# esp32-dev-board-v1_0.net
KiCad netlist of a schematic drawn in EasyEDA Pro
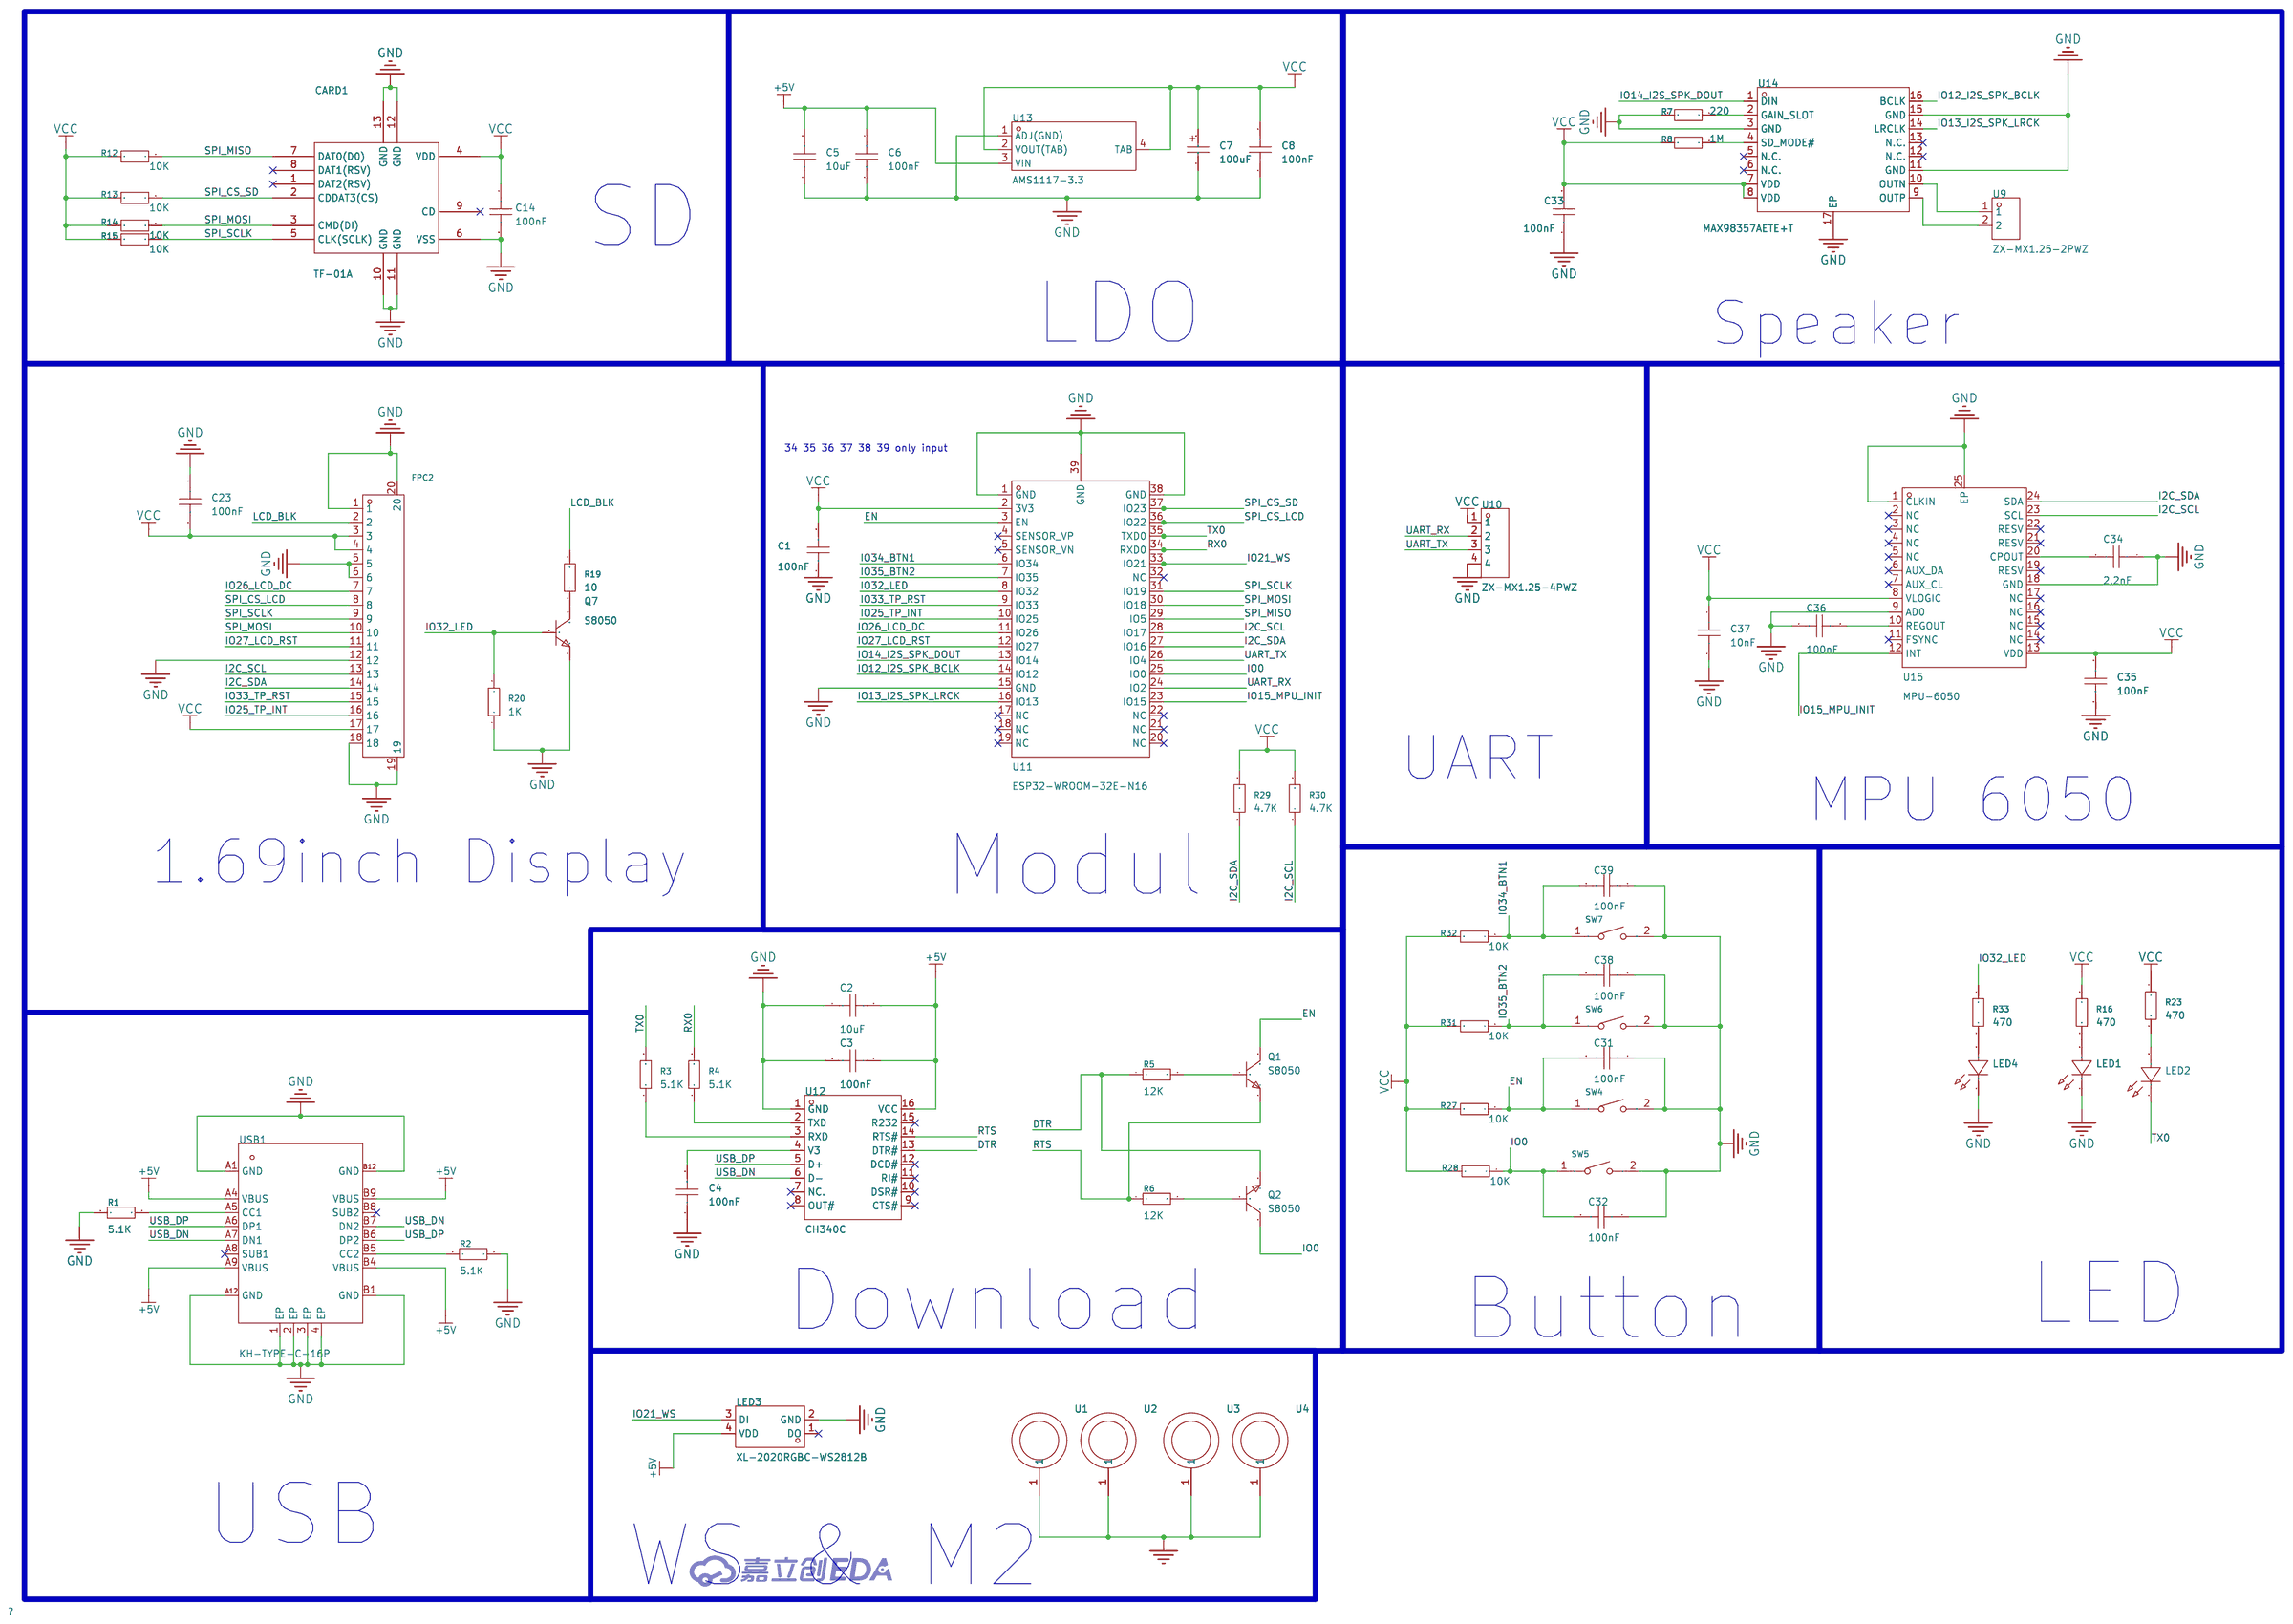
[diagram p0: schematic sheet]

(export (version "E")
  (design (tool "Eeschema 10.0.6"))
  (components
    (comp (ref "C1")
      (value "100nF")
      (footprint "easyedapro:C0402")
      (fields
        (field (name "Manufacturer Part") "CL05B104KO5NNNC")
        (field (name "Manufacturer") "SAMSUNG(三星)")
      )
      (libsource (lib "easyedapro") (part "CL05B104KO5NNNC"))
    )
    (comp (ref "C2")
      (value "10uF")
      (footprint "easyedapro:C0603")
      (fields
        (field (name "Manufacturer Part") "CGA0603X5R106K100JT")
        (field (name "Manufacturer") "HRE(芯声)")
      )
      (libsource (lib "easyedapro") (part "CGA0603X5R106K100JT"))
    )
    (comp (ref "C3")
      (value "100nF")
      (footprint "easyedapro:C0402")
      (fields
        (field (name "Manufacturer Part") "CL05B104KO5NNNC")
        (field (name "Manufacturer") "SAMSUNG(三星)")
      )
      (libsource (lib "easyedapro") (part "CL05B104KO5NNNC"))
    )
    (comp (ref "C4")
      (value "100nF")
      (footprint "easyedapro:C0402")
      (fields
        (field (name "Manufacturer Part") "CL05B104KO5NNNC")
        (field (name "Manufacturer") "SAMSUNG(三星)")
      )
      (libsource (lib "easyedapro") (part "CL05B104KO5NNNC"))
    )
    (comp (ref "C5")
      (value "10uF")
      (footprint "easyedapro:C0603")
      (fields
        (field (name "Manufacturer Part") "CGA0603X5R106K100JT")
        (field (name "Manufacturer") "HRE(芯声)")
      )
      (libsource (lib "easyedapro") (part "CGA0603X5R106K100JT"))
    )
    (comp (ref "C6")
      (value "100nF")
      (footprint "easyedapro:C0402")
      (fields
        (field (name "Manufacturer Part") "CL05B104KO5NNNC")
        (field (name "Manufacturer") "SAMSUNG(三星)")
      )
      (libsource (lib "easyedapro") (part "CL05B104KO5NNNC"))
    )
    (comp (ref "C7")
      (value "100uF")
      (footprint "easyedapro:CASE-B_3528")
      (fields (field (name "Manufacturer Part") "TAJB107K006RNJ") (field (name "Manufacturer") "Kyocera AVX"))
      (libsource (lib "easyedapro") (part "TAJB107K006RNJ"))
    )
    (comp (ref "C8")
      (value "100nF")
      (footprint "easyedapro:C0402")
      (fields
        (field (name "Manufacturer Part") "CL05B104KO5NNNC")
        (field (name "Manufacturer") "SAMSUNG(三星)")
      )
      (libsource (lib "easyedapro") (part "CL05B104KO5NNNC"))
    )
    (comp (ref "C14")
      (value "100nF")
      (footprint "easyedapro:C0402")
      (fields
        (field (name "Manufacturer Part") "CL05B104KO5NNNC")
        (field (name "Manufacturer") "SAMSUNG(三星)")
      )
      (libsource (lib "easyedapro") (part "CL05B104KO5NNNC"))
    )
    (comp (ref "C23")
      (value "100nF")
      (footprint "easyedapro:C0402")
      (fields
        (field (name "Manufacturer Part") "CL05B104KO5NNNC")
        (field (name "Manufacturer") "SAMSUNG(三星)")
      )
      (libsource (lib "easyedapro") (part "CL05B104KO5NNNC"))
    )
    (comp (ref "C31")
      (value "100nF")
      (footprint "easyedapro:C0402")
      (fields
        (field (name "Manufacturer Part") "CL05B104KO5NNNC")
        (field (name "Manufacturer") "SAMSUNG(三星)")
      )
      (libsource (lib "easyedapro") (part "CL05B104KO5NNNC"))
    )
    (comp (ref "C32")
      (value "100nF")
      (footprint "easyedapro:C0402")
      (fields
        (field (name "Manufacturer Part") "CL05B104KO5NNNC")
        (field (name "Manufacturer") "SAMSUNG(三星)")
      )
      (libsource (lib "easyedapro") (part "CL05B104KO5NNNC"))
    )
    (comp (ref "C33")
      (value "100nF")
      (footprint "easyedapro:C0402")
      (fields
        (field (name "Manufacturer Part") "CL05B104KO5NNNC")
        (field (name "Manufacturer") "SAMSUNG(三星)")
      )
      (libsource (lib "easyedapro") (part "CL05B104KO5NNNC"))
    )
    (comp (ref "C34")
      (value "2.2nF")
      (footprint "easyedapro:C0402")
      (fields
        (field (name "Manufacturer Part") "CL05B104KO5NNNC")
        (field (name "Manufacturer") "SAMSUNG(三星)")
      )
      (libsource (lib "easyedapro") (part "CL05B104KO5NNNC"))
    )
    (comp (ref "C35")
      (value "100nF")
      (footprint "easyedapro:C0402")
      (fields
        (field (name "Manufacturer Part") "CL05B104KO5NNNC")
        (field (name "Manufacturer") "SAMSUNG(三星)")
      )
      (libsource (lib "easyedapro") (part "CL05B104KO5NNNC"))
    )
    (comp (ref "C36")
      (value "100nF")
      (footprint "easyedapro:C0402")
      (fields
        (field (name "Manufacturer Part") "CL05B104KO5NNNC")
        (field (name "Manufacturer") "SAMSUNG(三星)")
      )
      (libsource (lib "easyedapro") (part "CL05B104KO5NNNC"))
    )
    (comp (ref "C37")
      (value "10nF")
      (footprint "easyedapro:C0402")
      (fields
        (field (name "Manufacturer Part") "CL05B104KO5NNNC")
        (field (name "Manufacturer") "SAMSUNG(三星)")
      )
      (libsource (lib "easyedapro") (part "CL05B104KO5NNNC"))
    )
    (comp (ref "C38")
      (value "100nF")
      (footprint "easyedapro:C0402")
      (fields
        (field (name "Manufacturer Part") "CL05B104KO5NNNC")
        (field (name "Manufacturer") "SAMSUNG(三星)")
      )
      (libsource (lib "easyedapro") (part "CL05B104KO5NNNC"))
    )
    (comp (ref "C39")
      (value "100nF")
      (footprint "easyedapro:C0402")
      (fields
        (field (name "Manufacturer Part") "CL05B104KO5NNNC")
        (field (name "Manufacturer") "SAMSUNG(三星)")
      )
      (libsource (lib "easyedapro") (part "CL05B104KO5NNNC"))
    )
    (comp (ref "CARD1")
      (value "TF-01A")
      (footprint "easyedapro:TF-SMD_TF-01A")
      (fields (field (name "Manufacturer") "韩国韩荣"))
      (libsource (lib "easyedapro") (part "TF-01A"))
    )
    (comp (ref "FPC2")
      (value "FPC-05F-18PH20")
      (footprint "easyedapro:FPC-SMD_18P-P0.50_FPC-05F-18PH20")
      (fields (field (name "Manufacturer") "XUNPU(讯普)"))
      (libsource (lib "easyedapro") (part "FPC-05F-18PH20"))
    )
    (comp (ref "LED1")
      (value "XL-1608SURC-06")
      (footprint "easyedapro:LED0603-RD_RED")
      (fields (field (name "Manufacturer") "XINGLIGHT(成兴光)"))
      (libsource (lib "easyedapro") (part "XL-1608SURC-06"))
    )
    (comp (ref "LED2")
      (value "XL-1608SURC-06")
      (footprint "easyedapro:LED0603-RD_RED")
      (fields (field (name "Manufacturer") "XINGLIGHT(成兴光)"))
      (libsource (lib "easyedapro") (part "XL-1608SURC-06"))
    )
    (comp (ref "LED3")
      (value "XL-2020RGBC-WS2812B")
      (footprint "easyedapro:LED-SMD_4P-L2.0-W2.0-BR-1")
      (fields (field (name "Manufacturer") "XINGLIGHT(成兴光)"))
      (libsource (lib "easyedapro") (part "XL-2020RGBC-WS2812B"))
    )
    (comp (ref "LED4")
      (value "XL-1608SURC-06")
      (footprint "easyedapro:LED0603-RD_RED")
      (fields (field (name "Manufacturer") "XINGLIGHT(成兴光)"))
      (libsource (lib "easyedapro") (part "XL-1608SURC-06"))
    )
    (comp (ref "Q1")
      (value "S8050")
      (footprint "easyedapro:SOT-23-3_L2.9-W1.3-P1.90-LS2.3-BR")
      (fields (field (name "Manufacturer") "宏迦橙"))
      (libsource (lib "easyedapro") (part "S8050_C20069125"))
    )
    (comp (ref "Q2")
      (value "S8050")
      (footprint "easyedapro:SOT-23-3_L2.9-W1.3-P1.90-LS2.3-BR")
      (fields (field (name "Manufacturer") "宏迦橙"))
      (libsource (lib "easyedapro") (part "S8050_C20069125"))
    )
    (comp (ref "Q7")
      (value "S8050")
      (fields (field (name "Manufacturer") "宏迦橙"))
      (libsource (lib "easyedapro") (part "S8050_C20069125"))
    )
    (comp (ref "R1")
      (value "5.1K")
      (footprint "easyedapro:R0402")
      (fields
        (field (name "Manufacturer Part") "0402WGF4700TCE")
        (field (name "Manufacturer") "UNI-ROYAL(厚声)")
      )
      (libsource (lib "easyedapro") (part "0402WGF4700TCE"))
    )
    (comp (ref "R2")
      (value "5.1K")
      (footprint "easyedapro:R0402")
      (fields
        (field (name "Manufacturer Part") "0402WGF4700TCE")
        (field (name "Manufacturer") "UNI-ROYAL(厚声)")
      )
      (libsource (lib "easyedapro") (part "0402WGF4700TCE"))
    )
    (comp (ref "R3")
      (value "5.1K")
      (footprint "easyedapro:R0402")
      (fields
        (field (name "Manufacturer Part") "0402WGF4700TCE")
        (field (name "Manufacturer") "UNI-ROYAL(厚声)")
      )
      (libsource (lib "easyedapro") (part "0402WGF4700TCE"))
    )
    (comp (ref "R4")
      (value "5.1K")
      (footprint "easyedapro:R0402")
      (fields
        (field (name "Manufacturer Part") "0402WGF4700TCE")
        (field (name "Manufacturer") "UNI-ROYAL(厚声)")
      )
      (libsource (lib "easyedapro") (part "0402WGF4700TCE"))
    )
    (comp (ref "R5")
      (value "12K")
      (footprint "easyedapro:R0402")
      (fields
        (field (name "Manufacturer Part") "0402WGF4700TCE")
        (field (name "Manufacturer") "UNI-ROYAL(厚声)")
      )
      (libsource (lib "easyedapro") (part "0402WGF4700TCE"))
    )
    (comp (ref "R6")
      (value "12K")
      (footprint "easyedapro:R0402")
      (fields
        (field (name "Manufacturer Part") "0402WGF4700TCE")
        (field (name "Manufacturer") "UNI-ROYAL(厚声)")
      )
      (libsource (lib "easyedapro") (part "0402WGF4700TCE"))
    )
    (comp (ref "R7")
      (value "220")
      (footprint "easyedapro:R0402")
      (fields
        (field (name "Manufacturer Part") "0402WGF4700TCE")
        (field (name "Manufacturer") "UNI-ROYAL(厚声)")
      )
      (libsource (lib "easyedapro") (part "0402WGF4700TCE"))
    )
    (comp (ref "R8")
      (value "1M")
      (footprint "easyedapro:R0402")
      (fields
        (field (name "Manufacturer Part") "0402WGF4700TCE")
        (field (name "Manufacturer") "UNI-ROYAL(厚声)")
      )
      (libsource (lib "easyedapro") (part "0402WGF4700TCE"))
    )
    (comp (ref "R12")
      (value "10K")
      (footprint "easyedapro:R0402")
      (fields
        (field (name "Manufacturer Part") "0402WGF4700TCE")
        (field (name "Manufacturer") "UNI-ROYAL(厚声)")
      )
      (libsource (lib "easyedapro") (part "0402WGF4700TCE"))
    )
    (comp (ref "R13")
      (value "10K")
      (footprint "easyedapro:R0402")
      (fields
        (field (name "Manufacturer Part") "0402WGF4700TCE")
        (field (name "Manufacturer") "UNI-ROYAL(厚声)")
      )
      (libsource (lib "easyedapro") (part "0402WGF4700TCE"))
    )
    (comp (ref "R14")
      (value "10K")
      (footprint "easyedapro:R0402")
      (fields
        (field (name "Manufacturer Part") "0402WGF4700TCE")
        (field (name "Manufacturer") "UNI-ROYAL(厚声)")
      )
      (libsource (lib "easyedapro") (part "0402WGF4700TCE"))
    )
    (comp (ref "R15")
      (value "10K")
      (footprint "easyedapro:R0402")
      (fields
        (field (name "Manufacturer Part") "0402WGF4700TCE")
        (field (name "Manufacturer") "UNI-ROYAL(厚声)")
      )
      (libsource (lib "easyedapro") (part "0402WGF4700TCE"))
    )
    (comp (ref "R16")
      (value "470")
      (footprint "easyedapro:R0402")
      (fields
        (field (name "Manufacturer Part") "0402WGF4700TCE")
        (field (name "Manufacturer") "UNI-ROYAL(厚声)")
      )
      (libsource (lib "easyedapro") (part "0402WGF4700TCE"))
    )
    (comp (ref "R19")
      (value "10")
      (footprint "easyedapro:R0402")
      (fields
        (field (name "Manufacturer Part") "0402WGF4700TCE")
        (field (name "Manufacturer") "UNI-ROYAL(厚声)")
      )
      (libsource (lib "easyedapro") (part "0402WGF4700TCE"))
    )
    (comp (ref "R20")
      (value "1K")
      (footprint "easyedapro:R0402")
      (fields
        (field (name "Manufacturer Part") "0402WGF4700TCE")
        (field (name "Manufacturer") "UNI-ROYAL(厚声)")
      )
      (libsource (lib "easyedapro") (part "0402WGF4700TCE"))
    )
    (comp (ref "R23")
      (value "470")
      (footprint "easyedapro:R0402")
      (fields
        (field (name "Manufacturer Part") "0402WGF4700TCE")
        (field (name "Manufacturer") "UNI-ROYAL(厚声)")
      )
      (libsource (lib "easyedapro") (part "0402WGF4700TCE"))
    )
    (comp (ref "R27")
      (value "10K")
      (footprint "easyedapro:R0402")
      (fields
        (field (name "Manufacturer Part") "0402WGF4700TCE")
        (field (name "Manufacturer") "UNI-ROYAL(厚声)")
      )
      (libsource (lib "easyedapro") (part "0402WGF4700TCE"))
    )
    (comp (ref "R28")
      (value "10K")
      (footprint "easyedapro:R0402")
      (fields
        (field (name "Manufacturer Part") "0402WGF4700TCE")
        (field (name "Manufacturer") "UNI-ROYAL(厚声)")
      )
      (libsource (lib "easyedapro") (part "0402WGF4700TCE"))
    )
    (comp (ref "R29")
      (value "4.7K")
      (footprint "easyedapro:R0402")
      (fields
        (field (name "Manufacturer Part") "0402WGF4700TCE")
        (field (name "Manufacturer") "UNI-ROYAL(厚声)")
      )
      (libsource (lib "easyedapro") (part "0402WGF4700TCE"))
    )
    (comp (ref "R30")
      (value "4.7K")
      (footprint "easyedapro:R0402")
      (fields
        (field (name "Manufacturer Part") "0402WGF4700TCE")
        (field (name "Manufacturer") "UNI-ROYAL(厚声)")
      )
      (libsource (lib "easyedapro") (part "0402WGF4700TCE"))
    )
    (comp (ref "R31")
      (value "10K")
      (footprint "easyedapro:R0402")
      (fields
        (field (name "Manufacturer Part") "0402WGF4700TCE")
        (field (name "Manufacturer") "UNI-ROYAL(厚声)")
      )
      (libsource (lib "easyedapro") (part "0402WGF4700TCE"))
    )
    (comp (ref "R32")
      (value "10K")
      (footprint "easyedapro:R0402")
      (fields
        (field (name "Manufacturer Part") "0402WGF4700TCE")
        (field (name "Manufacturer") "UNI-ROYAL(厚声)")
      )
      (libsource (lib "easyedapro") (part "0402WGF4700TCE"))
    )
    (comp (ref "R33")
      (value "470")
      (footprint "easyedapro:R0402")
      (fields
        (field (name "Manufacturer Part") "0402WGF4700TCE")
        (field (name "Manufacturer") "UNI-ROYAL(厚声)")
      )
      (libsource (lib "easyedapro") (part "0402WGF4700TCE"))
    )
    (comp (ref "SW4")
      (value "TS-1088-AR02016")
      (footprint "easyedapro:SW-SMD_L3.9-W3.0-P4.45")
      (fields (field (name "Manufacturer") "XUNPU(讯普)"))
      (libsource (lib "easyedapro") (part "TS-1088-AR02016"))
    )
    (comp (ref "SW5")
      (value "TS-1088-AR02016")
      (footprint "easyedapro:SW-SMD_L3.9-W3.0-P4.45")
      (fields (field (name "Manufacturer") "XUNPU(讯普)"))
      (libsource (lib "easyedapro") (part "TS-1088-AR02016"))
    )
    (comp (ref "SW6")
      (value "TS-1088-AR02016")
      (footprint "easyedapro:SW-SMD_L3.9-W3.0-P4.45")
      (fields (field (name "Manufacturer") "XUNPU(讯普)"))
      (libsource (lib "easyedapro") (part "TS-1088-AR02016"))
    )
    (comp (ref "SW7")
      (value "TS-1088-AR02016")
      (footprint "easyedapro:SW-SMD_L3.9-W3.0-P4.45")
      (fields (field (name "Manufacturer") "XUNPU(讯普)"))
      (libsource (lib "easyedapro") (part "TS-1088-AR02016"))
    )
    (comp (ref "U1") (value "~") (footprint "easyedapro:M2") (libsource (lib "easyedapro") (part "M2")))
    (comp (ref "U2") (value "~") (footprint "easyedapro:M2") (libsource (lib "easyedapro") (part "M2")))
    (comp (ref "U3") (value "~") (footprint "easyedapro:M2") (libsource (lib "easyedapro") (part "M2")))
    (comp (ref "U4") (value "~") (footprint "easyedapro:M2") (libsource (lib "easyedapro") (part "M2")))
    (comp (ref "U9")
      (value "ZX-MX1.25-2PWZ")
      (footprint "easyedapro:CONN-TH_2P-P1.25_ZX-MX1.25-2PWZ")
      (fields (field (name "Manufacturer") "Megastar(兆星)"))
      (libsource (lib "easyedapro") (part "ZX-MX1.25-2PWZ"))
    )
    (comp (ref "U10")
      (value "ZX-MX1.25-4PWZ")
      (footprint "easyedapro:CONN-TH_4P-P1.25_ZX-MX1.25-4PWZ")
      (fields (field (name "Manufacturer") "Megastar(兆星)"))
      (libsource (lib "easyedapro") (part "ZX-MX1.25-4PWZ"))
    )
    (comp (ref "U11")
      (value "ESP32-WROOM-32E-N16")
      (footprint "easyedapro:WIFI-SMD_ESP32-WROOM-32E")
      (fields (field (name "Manufacturer") "ESPRESSIF(乐鑫)"))
      (libsource (lib "easyedapro") (part "ESP32-WROOM-32E(16MB)"))
    )
    (comp (ref "U12")
      (value "CH340C")
      (footprint "easyedapro:SOP-16_L10.0-W3.9-P1.27-LS6.0-BL")
      (fields (field (name "Manufacturer") "WCH(南京沁恒)"))
      (libsource (lib "easyedapro") (part "CH340C"))
    )
    (comp (ref "U13")
      (value "AMS1117-3.3")
      (footprint "easyedapro:SOT-223-4_L6.5-W3.5-P2.30-LS7.0-BR")
      (fields (field (name "Manufacturer") "UMW(友台半导体)"))
      (libsource (lib "easyedapro") (part "AMS1117-3.3_C347222"))
    )
    (comp (ref "U14")
      (value "MAX98357AETE+T")
      (footprint "easyedapro:TQFN-16_L3.0-W3.0-P0.50-BL-EP1.5")
      (fields (field (name "Manufacturer") "ADI(亚德诺)/MAXIM(美信)"))
      (libsource (lib "easyedapro") (part "MAX98357AETE+T"))
    )
    (comp (ref "U15")
      (value "MPU-6050")
      (footprint "easyedapro:QFN-24_L4.0-W4.0-P0.50-BL-EP2.7")
      (description "Sensor Type:加速度计陀螺仪 Operating Temperature:-40°C~+85°C Operating Temperature:-40°C~+85°C")
      (fields (field (name "Manufacturer") "TDK InvenSense(应美盛)"))
      (libsource (lib "easyedapro") (part "MPU-6050_C24112"))
    )
    (comp (ref "USB1")
      (value "KH-TYPE-C-16P")
      (footprint "easyedapro:USB-C-SMD_KH-TYPE-C-16P")
      (fields (field (name "Manufacturer") "kinghelm(金航标)"))
      (libsource (lib "easyedapro") (part "KH-TYPE-C-16P"))
    )
  )
  (nets
    (net (code "1") (name "+5V") (class "Default")
      (node (ref "C2") (pin "2") (pinfunction "2_2") (pintype "unspecified"))
      (node (ref "C3") (pin "1") (pinfunction "1_1") (pintype "unspecified"))
      (node (ref "C5") (pin "2") (pinfunction "2_2") (pintype "unspecified"))
      (node (ref "C6") (pin "1") (pinfunction "1_1") (pintype "unspecified"))
      (node (ref "LED3") (pin "4") (pinfunction "VDD_4") (pintype "unspecified"))
      (node (ref "U12") (pin "16") (pinfunction "VCC_16") (pintype "unspecified"))
      (node (ref "U13") (pin "3") (pinfunction "VIN_3") (pintype "unspecified"))
      (node (ref "USB1") (pin "A4") (pinfunction "VBUS_A4") (pintype "unspecified"))
      (node (ref "USB1") (pin "A9") (pinfunction "VBUS_A9") (pintype "unspecified"))
      (node (ref "USB1") (pin "B4") (pinfunction "VBUS_B4") (pintype "unspecified"))
      (node (ref "USB1") (pin "B9") (pinfunction "VBUS_B9") (pintype "unspecified"))
    )
    (net (code "2") (name "/DTR") (class "Default")
      (node (ref "Q2") (pin "2") (pinfunction "E_2") (pintype "input"))
      (node (ref "R5") (pin "1") (pinfunction "1_1") (pintype "input"))
      (node (ref "U12") (pin "13") (pinfunction "DTR#_13") (pintype "unspecified"))
    )
    (net (code "3") (name "/EN") (class "Default")
      (node (ref "C31") (pin "2") (pinfunction "2_2") (pintype "unspecified"))
      (node (ref "Q1") (pin "3") (pinfunction "C_3") (pintype "input"))
      (node (ref "R27") (pin "1") (pinfunction "1_1") (pintype "input"))
      (node (ref "SW4") (pin "1") (pinfunction "1_1") (pintype "input"))
      (node (ref "U11") (pin "3") (pinfunction "EN_3") (pintype "unspecified"))
    )
    (net (code "4") (name "/I2C_SCL") (class "Default")
      (node (ref "FPC2") (pin "13") (pinfunction "13_13") (pintype "input"))
      (node (ref "R30") (pin "1") (pinfunction "1_1") (pintype "input"))
      (node (ref "U11") (pin "28") (pinfunction "IO17_28") (pintype "unspecified"))
      (node (ref "U15") (pin "23") (pinfunction "SCL_23") (pintype "unspecified"))
    )
    (net (code "5") (name "/I2C_SDA") (class "Default")
      (node (ref "FPC2") (pin "14") (pinfunction "14_14") (pintype "input"))
      (node (ref "R29") (pin "1") (pinfunction "1_1") (pintype "input"))
      (node (ref "U11") (pin "27") (pinfunction "IO16_27") (pintype "unspecified"))
      (node (ref "U15") (pin "24") (pinfunction "SDA_24") (pintype "unspecified"))
    )
    (net (code "6") (name "/IO0") (class "Default")
      (node (ref "C32") (pin "2") (pinfunction "2_2") (pintype "unspecified"))
      (node (ref "Q2") (pin "3") (pinfunction "C_3") (pintype "input"))
      (node (ref "R28") (pin "1") (pinfunction "1_1") (pintype "input"))
      (node (ref "SW5") (pin "1") (pinfunction "1_1") (pintype "input"))
      (node (ref "U11") (pin "25") (pinfunction "IO0_25") (pintype "unspecified"))
    )
    (net (code "7") (name "/IO12_I2S_SPK_BCLK") (class "Default")
      (node (ref "U11") (pin "14") (pinfunction "IO12_14") (pintype "unspecified"))
      (node (ref "U14") (pin "16") (pinfunction "BCLK_16") (pintype "unspecified"))
    )
    (net (code "8") (name "/IO13_I2S_SPK_LRCK") (class "Default")
      (node (ref "U11") (pin "16") (pinfunction "IO13_16") (pintype "unspecified"))
      (node (ref "U14") (pin "14") (pinfunction "LRCLK_14") (pintype "unspecified"))
    )
    (net (code "9") (name "/IO14_I2S_SPK_DOUT") (class "Default")
      (node (ref "U11") (pin "13") (pinfunction "IO14_13") (pintype "unspecified"))
      (node (ref "U14") (pin "1") (pinfunction "DIN_1") (pintype "unspecified"))
    )
    (net (code "10") (name "/IO15_MPU_INIT") (class "Default")
      (node (ref "U11") (pin "23") (pinfunction "IO15_23") (pintype "unspecified"))
      (node (ref "U15") (pin "12") (pinfunction "INT_12") (pintype "unspecified"))
    )
    (net (code "11") (name "/IO21_WS") (class "Default")
      (node (ref "LED3") (pin "3") (pinfunction "DI_3") (pintype "unspecified"))
      (node (ref "U11") (pin "33") (pinfunction "IO21_33") (pintype "unspecified"))
    )
    (net (code "12") (name "/IO25_TP_INT") (class "Default")
      (node (ref "FPC2") (pin "16") (pinfunction "16_16") (pintype "input"))
      (node (ref "U11") (pin "10") (pinfunction "IO25_10") (pintype "unspecified"))
    )
    (net (code "13") (name "/IO26_LCD_DC") (class "Default")
      (node (ref "FPC2") (pin "7") (pinfunction "7_7") (pintype "input"))
      (node (ref "U11") (pin "11") (pinfunction "IO26_11") (pintype "unspecified"))
    )
    (net (code "14") (name "/IO27_LCD_RST") (class "Default")
      (node (ref "FPC2") (pin "11") (pinfunction "11_11") (pintype "input"))
      (node (ref "U11") (pin "12") (pinfunction "IO27_12") (pintype "unspecified"))
    )
    (net (code "15") (name "/IO32_LED") (class "Default")
      (node (ref "Q7") (pin "1") (pinfunction "B_1") (pintype "input"))
      (node (ref "R20") (pin "2") (pinfunction "2_2") (pintype "input"))
      (node (ref "R33") (pin "1") (pinfunction "1_1") (pintype "input"))
      (node (ref "U11") (pin "8") (pinfunction "IO32_8") (pintype "unspecified"))
    )
    (net (code "16") (name "/IO33_TP_RST") (class "Default")
      (node (ref "FPC2") (pin "15") (pinfunction "15_15") (pintype "input"))
      (node (ref "U11") (pin "9") (pinfunction "IO33_9") (pintype "unspecified"))
    )
    (net (code "17") (name "/IO34_BTN1") (class "Default")
      (node (ref "C39") (pin "2") (pinfunction "2_2") (pintype "unspecified"))
      (node (ref "R32") (pin "1") (pinfunction "1_1") (pintype "input"))
      (node (ref "SW7") (pin "1") (pinfunction "1_1") (pintype "input"))
      (node (ref "U11") (pin "6") (pinfunction "IO34_6") (pintype "unspecified"))
    )
    (net (code "18") (name "/IO35_BTN2") (class "Default")
      (node (ref "C38") (pin "2") (pinfunction "2_2") (pintype "unspecified"))
      (node (ref "R31") (pin "1") (pinfunction "1_1") (pintype "input"))
      (node (ref "SW6") (pin "1") (pinfunction "1_1") (pintype "input"))
      (node (ref "U11") (pin "7") (pinfunction "IO35_7") (pintype "unspecified"))
    )
    (net (code "19") (name "/LCD_BLK") (class "Default")
      (node (ref "FPC2") (pin "2") (pinfunction "2_2") (pintype "input"))
      (node (ref "R19") (pin "2") (pinfunction "2_2") (pintype "input"))
    )
    (net (code "20") (name "/RTS") (class "Default")
      (node (ref "Q1") (pin "2") (pinfunction "E_2") (pintype "input"))
      (node (ref "R6") (pin "1") (pinfunction "1_1") (pintype "input"))
      (node (ref "U12") (pin "14") (pinfunction "RTS#_14") (pintype "unspecified"))
    )
    (net (code "21") (name "/RX0") (class "Default")
      (node (ref "R4") (pin "2") (pinfunction "2_2") (pintype "input"))
      (node (ref "U11") (pin "34") (pinfunction "RXD0_34") (pintype "unspecified"))
    )
    (net (code "22") (name "/SPI_CS_LCD") (class "Default")
      (node (ref "FPC2") (pin "8") (pinfunction "8_8") (pintype "input"))
      (node (ref "U11") (pin "36") (pinfunction "IO22_36") (pintype "unspecified"))
    )
    (net (code "23") (name "/SPI_CS_SD") (class "Default")
      (node (ref "CARD1") (pin "2") (pinfunction "CDDAT3(CS)_2") (pintype "bidirectional"))
      (node (ref "R13") (pin "1") (pinfunction "1_1") (pintype "input"))
      (node (ref "U11") (pin "37") (pinfunction "IO23_37") (pintype "unspecified"))
    )
    (net (code "24") (name "/SPI_MISO") (class "Default")
      (node (ref "CARD1") (pin "7") (pinfunction "DAT0(D0)_7") (pintype "bidirectional"))
      (node (ref "R12") (pin "1") (pinfunction "1_1") (pintype "input"))
      (node (ref "U11") (pin "29") (pinfunction "IO5_29") (pintype "unspecified"))
    )
    (net (code "25") (name "/SPI_MOSI") (class "Default")
      (node (ref "CARD1") (pin "3") (pinfunction "CMD(DI)_3") (pintype "input"))
      (node (ref "FPC2") (pin "10") (pinfunction "10_10") (pintype "input"))
      (node (ref "R14") (pin "1") (pinfunction "1_1") (pintype "input"))
      (node (ref "U11") (pin "30") (pinfunction "IO18_30") (pintype "unspecified"))
    )
    (net (code "26") (name "/SPI_SCLK") (class "Default")
      (node (ref "CARD1") (pin "5") (pinfunction "CLK(SCLK)_5") (pintype "input"))
      (node (ref "FPC2") (pin "9") (pinfunction "9_9") (pintype "input"))
      (node (ref "R15") (pin "1") (pinfunction "1_1") (pintype "input"))
      (node (ref "U11") (pin "31") (pinfunction "IO19_31") (pintype "unspecified"))
    )
    (net (code "27") (name "/TX0") (class "Default")
      (node (ref "LED2") (pin "1") (pinfunction "K_1") (pintype "unspecified"))
      (node (ref "R3") (pin "2") (pinfunction "2_2") (pintype "input"))
      (node (ref "U11") (pin "35") (pinfunction "TXD0_35") (pintype "unspecified"))
    )
    (net (code "28") (name "/UART_RX") (class "Default")
      (node (ref "U10") (pin "2") (pinfunction "2_2") (pintype "unspecified"))
      (node (ref "U11") (pin "24") (pinfunction "IO2_24") (pintype "unspecified"))
    )
    (net (code "29") (name "/UART_TX") (class "Default")
      (node (ref "U10") (pin "3") (pinfunction "3_3") (pintype "unspecified"))
      (node (ref "U11") (pin "26") (pinfunction "IO4_26") (pintype "unspecified"))
    )
    (net (code "30") (name "/USB_DN") (class "Default")
      (node (ref "U12") (pin "6") (pinfunction "D-_6") (pintype "unspecified"))
      (node (ref "USB1") (pin "A7") (pinfunction "DN1_A7") (pintype "unspecified"))
      (node (ref "USB1") (pin "B7") (pinfunction "DN2_B7") (pintype "unspecified"))
    )
    (net (code "31") (name "/USB_DP") (class "Default")
      (node (ref "U12") (pin "5") (pinfunction "D+_5") (pintype "unspecified"))
      (node (ref "USB1") (pin "A6") (pinfunction "DP1_A6") (pintype "unspecified"))
      (node (ref "USB1") (pin "B6") (pinfunction "DP2_B6") (pintype "unspecified"))
    )
    (net (code "32") (name "GND") (class "Default")
      (node (ref "C1") (pin "1") (pinfunction "1_1") (pintype "unspecified"))
      (node (ref "C14") (pin "2") (pinfunction "2_2") (pintype "unspecified"))
      (node (ref "C2") (pin "1") (pinfunction "1_1") (pintype "unspecified"))
      (node (ref "C23") (pin "1") (pinfunction "1_1") (pintype "unspecified"))
      (node (ref "C3") (pin "2") (pinfunction "2_2") (pintype "unspecified"))
      (node (ref "C31") (pin "1") (pinfunction "1_1") (pintype "unspecified"))
      (node (ref "C32") (pin "1") (pinfunction "1_1") (pintype "unspecified"))
      (node (ref "C33") (pin "1") (pinfunction "1_1") (pintype "unspecified"))
      (node (ref "C34") (pin "1") (pinfunction "1_1") (pintype "unspecified"))
      (node (ref "C35") (pin "2") (pinfunction "2_2") (pintype "unspecified"))
      (node (ref "C36") (pin "1") (pinfunction "1_1") (pintype "unspecified"))
      (node (ref "C37") (pin "2") (pinfunction "2_2") (pintype "unspecified"))
      (node (ref "C38") (pin "1") (pinfunction "1_1") (pintype "unspecified"))
      (node (ref "C39") (pin "1") (pinfunction "1_1") (pintype "unspecified"))
      (node (ref "C4") (pin "1") (pinfunction "1_1") (pintype "unspecified"))
      (node (ref "C5") (pin "1") (pinfunction "1_1") (pintype "unspecified"))
      (node (ref "C6") (pin "2") (pinfunction "2_2") (pintype "unspecified"))
      (node (ref "C7") (pin "2") (pinfunction "2_2") (pintype "input"))
      (node (ref "C8") (pin "1") (pinfunction "1_1") (pintype "unspecified"))
      (node (ref "CARD1") (pin "10") (pinfunction "GND_10") (pintype "input"))
      (node (ref "CARD1") (pin "11") (pinfunction "GND_11") (pintype "input"))
      (node (ref "CARD1") (pin "12") (pinfunction "GND_12") (pintype "input"))
      (node (ref "CARD1") (pin "13") (pinfunction "GND_13") (pintype "input"))
      (node (ref "CARD1") (pin "6") (pinfunction "VSS_6") (pintype "input"))
      (node (ref "FPC2") (pin "1") (pinfunction "1_1") (pintype "input"))
      (node (ref "FPC2") (pin "12") (pinfunction "12_12") (pintype "input"))
      (node (ref "FPC2") (pin "18") (pinfunction "18_18") (pintype "input"))
      (node (ref "FPC2") (pin "19") (pinfunction "19_19") (pintype "input"))
      (node (ref "FPC2") (pin "20") (pinfunction "20_20") (pintype "input"))
      (node (ref "FPC2") (pin "5") (pinfunction "5_5") (pintype "input"))
      (node (ref "FPC2") (pin "6") (pinfunction "6_6") (pintype "input"))
      (node (ref "LED1") (pin "1") (pinfunction "K_1") (pintype "unspecified"))
      (node (ref "LED3") (pin "2") (pinfunction "GND_2") (pintype "unspecified"))
      (node (ref "LED4") (pin "1") (pinfunction "K_1") (pintype "unspecified"))
      (node (ref "Q7") (pin "2") (pinfunction "E_2") (pintype "input"))
      (node (ref "R1") (pin "1") (pinfunction "1_1") (pintype "input"))
      (node (ref "R2") (pin "2") (pinfunction "2_2") (pintype "input"))
      (node (ref "R20") (pin "1") (pinfunction "1_1") (pintype "input"))
      (node (ref "R7") (pin "2") (pinfunction "2_2") (pintype "input"))
      (node (ref "SW4") (pin "2") (pinfunction "2_2") (pintype "input"))
      (node (ref "SW5") (pin "2") (pinfunction "2_2") (pintype "input"))
      (node (ref "SW6") (pin "2") (pinfunction "2_2") (pintype "input"))
      (node (ref "SW7") (pin "2") (pinfunction "2_2") (pintype "input"))
      (node (ref "U1") (pin "1") (pinfunction "1_1") (pintype "input"))
      (node (ref "U10") (pin "4") (pinfunction "4_4") (pintype "unspecified"))
      (node (ref "U11") (pin "1") (pinfunction "GND_1") (pintype "unspecified"))
      (node (ref "U11") (pin "15") (pinfunction "GND_15") (pintype "unspecified"))
      (node (ref "U11") (pin "38") (pinfunction "GND_38") (pintype "unspecified"))
      (node (ref "U11") (pin "39") (pinfunction "GND_39") (pintype "unspecified"))
      (node (ref "U12") (pin "1") (pinfunction "GND_1") (pintype "unspecified"))
      (node (ref "U13") (pin "1") (pinfunction "ADJ(GND)_1") (pintype "unspecified"))
      (node (ref "U14") (pin "11") (pinfunction "GND_11") (pintype "unspecified"))
      (node (ref "U14") (pin "15") (pinfunction "GND_15") (pintype "unspecified"))
      (node (ref "U14") (pin "17") (pinfunction "EP_17") (pintype "unspecified"))
      (node (ref "U14") (pin "3") (pinfunction "GND_3") (pintype "unspecified"))
      (node (ref "U15") (pin "1") (pinfunction "CLKIN_1") (pintype "unspecified"))
      (node (ref "U15") (pin "18") (pinfunction "GND_18") (pintype "unspecified"))
      (node (ref "U15") (pin "25") (pinfunction "EP_25") (pintype "unspecified"))
      (node (ref "U15") (pin "9") (pinfunction "AD0_9") (pintype "unspecified"))
      (node (ref "U2") (pin "1") (pinfunction "1_1") (pintype "input"))
      (node (ref "U3") (pin "1") (pinfunction "1_1") (pintype "input"))
      (node (ref "U4") (pin "1") (pinfunction "1_1") (pintype "input"))
      (node (ref "USB1") (pin "1") (pinfunction "EP_1") (pintype "unspecified"))
      (node (ref "USB1") (pin "2") (pinfunction "EP_2") (pintype "unspecified"))
      (node (ref "USB1") (pin "3") (pinfunction "EP_3") (pintype "unspecified"))
      (node (ref "USB1") (pin "4") (pinfunction "EP_4") (pintype "unspecified"))
      (node (ref "USB1") (pin "A1") (pinfunction "GND_A1") (pintype "unspecified"))
      (node (ref "USB1") (pin "A12") (pinfunction "GND_A12") (pintype "unspecified"))
      (node (ref "USB1") (pin "B1") (pinfunction "GND_B1") (pintype "unspecified"))
      (node (ref "USB1") (pin "B12") (pinfunction "GND_B12") (pintype "unspecified"))
    )
    (net (code "33") (name "Net-(LED1-A)") (class "Default")
      (node (ref "LED1") (pin "2") (pinfunction "A_2") (pintype "unspecified"))
      (node (ref "R16") (pin "2") (pinfunction "2_2") (pintype "input"))
    )
    (net (code "34") (name "Net-(LED2-A)") (class "Default")
      (node (ref "LED2") (pin "2") (pinfunction "A_2") (pintype "unspecified"))
      (node (ref "R23") (pin "2") (pinfunction "2_2") (pintype "input"))
    )
    (net (code "35") (name "Net-(LED4-A)") (class "Default")
      (node (ref "LED4") (pin "2") (pinfunction "A_2") (pintype "unspecified"))
      (node (ref "R33") (pin "2") (pinfunction "2_2") (pintype "input"))
    )
    (net (code "36") (name "Net-(Q1-B)") (class "Default")
      (node (ref "Q1") (pin "1") (pinfunction "B_1") (pintype "input"))
      (node (ref "R5") (pin "2") (pinfunction "2_2") (pintype "input"))
    )
    (net (code "37") (name "Net-(Q2-B)") (class "Default")
      (node (ref "Q2") (pin "1") (pinfunction "B_1") (pintype "input"))
      (node (ref "R6") (pin "2") (pinfunction "2_2") (pintype "input"))
    )
    (net (code "38") (name "Net-(Q7-C)") (class "Default")
      (node (ref "Q7") (pin "3") (pinfunction "C_3") (pintype "input"))
      (node (ref "R19") (pin "1") (pinfunction "1_1") (pintype "input"))
    )
    (net (code "39") (name "Net-(U12-RXD)") (class "Default")
      (node (ref "R3") (pin "1") (pinfunction "1_1") (pintype "input"))
      (node (ref "U12") (pin "3") (pinfunction "RXD_3") (pintype "unspecified"))
    )
    (net (code "40") (name "Net-(U12-TXD)") (class "Default")
      (node (ref "R4") (pin "1") (pinfunction "1_1") (pintype "input"))
      (node (ref "U12") (pin "2") (pinfunction "TXD_2") (pintype "unspecified"))
    )
    (net (code "41") (name "Net-(U12-V3)") (class "Default")
      (node (ref "C4") (pin "2") (pinfunction "2_2") (pintype "unspecified"))
      (node (ref "U12") (pin "4") (pinfunction "V3_4") (pintype "unspecified"))
    )
    (net (code "42") (name "Net-(U14-GAIN_SLOT)") (class "Default")
      (node (ref "R7") (pin "1") (pinfunction "1_1") (pintype "input"))
      (node (ref "U14") (pin "2") (pinfunction "GAIN_SLOT_2") (pintype "unspecified"))
    )
    (net (code "43") (name "Net-(U14-OUTN)") (class "Default")
      (node (ref "U14") (pin "10") (pinfunction "OUTN_10") (pintype "unspecified"))
      (node (ref "U9") (pin "1") (pinfunction "1_1") (pintype "unspecified"))
    )
    (net (code "44") (name "Net-(U14-OUTP)") (class "Default")
      (node (ref "U14") (pin "9") (pinfunction "OUTP_9") (pintype "unspecified"))
      (node (ref "U9") (pin "2") (pinfunction "2_2") (pintype "unspecified"))
    )
    (net (code "45") (name "Net-(U14-SD_MODE#)") (class "Default")
      (node (ref "R8") (pin "1") (pinfunction "1_1") (pintype "input"))
      (node (ref "U14") (pin "4") (pinfunction "SD_MODE#_4") (pintype "unspecified"))
    )
    (net (code "46") (name "Net-(U15-CPOUT)") (class "Default")
      (node (ref "C34") (pin "2") (pinfunction "2_2") (pintype "unspecified"))
      (node (ref "U15") (pin "20") (pinfunction "CPOUT_20") (pintype "unspecified"))
    )
    (net (code "47") (name "Net-(U15-REGOUT)") (class "Default")
      (node (ref "C36") (pin "2") (pinfunction "2_2") (pintype "unspecified"))
      (node (ref "U15") (pin "10") (pinfunction "REGOUT_10") (pintype "unspecified"))
    )
    (net (code "48") (name "Net-(USB1-CC1)") (class "Default")
      (node (ref "R1") (pin "2") (pinfunction "2_2") (pintype "input"))
      (node (ref "USB1") (pin "A5") (pinfunction "CC1_A5") (pintype "unspecified"))
    )
    (net (code "49") (name "Net-(USB1-CC2)") (class "Default")
      (node (ref "R2") (pin "1") (pinfunction "1_1") (pintype "input"))
      (node (ref "USB1") (pin "B5") (pinfunction "CC2_B5") (pintype "unspecified"))
    )
    (net (code "50") (name "VCC") (class "Default")
      (node (ref "C1") (pin "2") (pinfunction "2_2") (pintype "unspecified"))
      (node (ref "C14") (pin "1") (pinfunction "1_1") (pintype "unspecified"))
      (node (ref "C23") (pin "2") (pinfunction "2_2") (pintype "unspecified"))
      (node (ref "C33") (pin "2") (pinfunction "2_2") (pintype "unspecified"))
      (node (ref "C35") (pin "1") (pinfunction "1_1") (pintype "unspecified"))
      (node (ref "C37") (pin "1") (pinfunction "1_1") (pintype "unspecified"))
      (node (ref "C7") (pin "1") (pinfunction "1_1") (pintype "input"))
      (node (ref "C8") (pin "2") (pinfunction "2_2") (pintype "unspecified"))
      (node (ref "CARD1") (pin "4") (pinfunction "VDD_4") (pintype "input"))
      (node (ref "FPC2") (pin "17") (pinfunction "17_17") (pintype "input"))
      (node (ref "FPC2") (pin "3") (pinfunction "3_3") (pintype "input"))
      (node (ref "FPC2") (pin "4") (pinfunction "4_4") (pintype "input"))
      (node (ref "R12") (pin "2") (pinfunction "2_2") (pintype "input"))
      (node (ref "R13") (pin "2") (pinfunction "2_2") (pintype "input"))
      (node (ref "R14") (pin "2") (pinfunction "2_2") (pintype "input"))
      (node (ref "R15") (pin "2") (pinfunction "2_2") (pintype "input"))
      (node (ref "R16") (pin "1") (pinfunction "1_1") (pintype "input"))
      (node (ref "R23") (pin "1") (pinfunction "1_1") (pintype "input"))
      (node (ref "R27") (pin "2") (pinfunction "2_2") (pintype "input"))
      (node (ref "R28") (pin "2") (pinfunction "2_2") (pintype "input"))
      (node (ref "R29") (pin "2") (pinfunction "2_2") (pintype "input"))
      (node (ref "R30") (pin "2") (pinfunction "2_2") (pintype "input"))
      (node (ref "R31") (pin "2") (pinfunction "2_2") (pintype "input"))
      (node (ref "R32") (pin "2") (pinfunction "2_2") (pintype "input"))
      (node (ref "R8") (pin "2") (pinfunction "2_2") (pintype "input"))
      (node (ref "U10") (pin "1") (pinfunction "1_1") (pintype "unspecified"))
      (node (ref "U11") (pin "2") (pinfunction "3V3_2") (pintype "unspecified"))
      (node (ref "U13") (pin "2") (pinfunction "VOUT(TAB)_2") (pintype "unspecified"))
      (node (ref "U13") (pin "4") (pinfunction "TAB_4") (pintype "unspecified"))
      (node (ref "U14") (pin "7") (pinfunction "VDD_7") (pintype "unspecified"))
      (node (ref "U14") (pin "8") (pinfunction "VDD_8") (pintype "unspecified"))
      (node (ref "U15") (pin "13") (pinfunction "VDD_13") (pintype "unspecified"))
      (node (ref "U15") (pin "8") (pinfunction "VLOGIC_8") (pintype "unspecified"))
    )
    (net (code "51") (name "unconnected-(CARD1-CD-Pad9)") (class "Default")
      (node (ref "CARD1") (pin "9") (pinfunction "CD_9") (pintype "input+no_connect"))
    )
    (net (code "52") (name "unconnected-(CARD1-DAT1(RSV)-Pad8)") (class "Default")
      (node (ref "CARD1") (pin "8") (pinfunction "DAT1(RSV)_8") (pintype "bidirectional+no_connect"))
    )
    (net (code "53") (name "unconnected-(CARD1-DAT2(RSV)-Pad1)") (class "Default")
      (node (ref "CARD1") (pin "1") (pinfunction "DAT2(RSV)_1") (pintype "bidirectional+no_connect"))
    )
    (net (code "54") (name "unconnected-(LED3-DO-Pad1)") (class "Default")
      (node (ref "LED3") (pin "1") (pinfunction "DO_1") (pintype "unspecified+no_connect"))
    )
    (net (code "55") (name "unconnected-(U11-NC-Pad17)") (class "Default")
      (node (ref "U11") (pin "17") (pinfunction "NC_17") (pintype "unspecified+no_connect"))
    )
    (net (code "56") (name "unconnected-(U11-NC-Pad18)") (class "Default")
      (node (ref "U11") (pin "18") (pinfunction "NC_18") (pintype "unspecified+no_connect"))
    )
    (net (code "57") (name "unconnected-(U11-NC-Pad19)") (class "Default")
      (node (ref "U11") (pin "19") (pinfunction "NC_19") (pintype "unspecified+no_connect"))
    )
    (net (code "58") (name "unconnected-(U11-NC-Pad20)") (class "Default")
      (node (ref "U11") (pin "20") (pinfunction "NC_20") (pintype "unspecified+no_connect"))
    )
    (net (code "59") (name "unconnected-(U11-NC-Pad21)") (class "Default")
      (node (ref "U11") (pin "21") (pinfunction "NC_21") (pintype "unspecified+no_connect"))
    )
    (net (code "60") (name "unconnected-(U11-NC-Pad22)") (class "Default")
      (node (ref "U11") (pin "22") (pinfunction "NC_22") (pintype "unspecified+no_connect"))
    )
    (net (code "61") (name "unconnected-(U11-NC-Pad32)") (class "Default")
      (node (ref "U11") (pin "32") (pinfunction "NC_32") (pintype "unspecified+no_connect"))
    )
    (net (code "62") (name "unconnected-(U11-SENSOR_VN-Pad5)") (class "Default")
      (node (ref "U11") (pin "5") (pinfunction "SENSOR_VN_5") (pintype "unspecified+no_connect"))
    )
    (net (code "63") (name "unconnected-(U11-SENSOR_VP-Pad4)") (class "Default")
      (node (ref "U11") (pin "4") (pinfunction "SENSOR_VP_4") (pintype "unspecified+no_connect"))
    )
    (net (code "64") (name "unconnected-(U12-CTS#-Pad9)") (class "Default")
      (node (ref "U12") (pin "9") (pinfunction "CTS#_9") (pintype "unspecified+no_connect"))
    )
    (net (code "65") (name "unconnected-(U12-DCD#-Pad12)") (class "Default")
      (node (ref "U12") (pin "12") (pinfunction "DCD#_12") (pintype "unspecified+no_connect"))
    )
    (net (code "66") (name "unconnected-(U12-DSR#-Pad10)") (class "Default")
      (node (ref "U12") (pin "10") (pinfunction "DSR#_10") (pintype "unspecified+no_connect"))
    )
    (net (code "67") (name "unconnected-(U12-NC.-Pad7)") (class "Default")
      (node (ref "U12") (pin "7") (pinfunction "NC._7") (pintype "unspecified+no_connect"))
    )
    (net (code "68") (name "unconnected-(U12-OUT#-Pad8)") (class "Default")
      (node (ref "U12") (pin "8") (pinfunction "OUT#_8") (pintype "unspecified+no_connect"))
    )
    (net (code "69") (name "unconnected-(U12-R232-Pad15)") (class "Default")
      (node (ref "U12") (pin "15") (pinfunction "R232_15") (pintype "unspecified+no_connect"))
    )
    (net (code "70") (name "unconnected-(U12-RI#-Pad11)") (class "Default")
      (node (ref "U12") (pin "11") (pinfunction "RI#_11") (pintype "unspecified+no_connect"))
    )
    (net (code "71") (name "unconnected-(U14-N.C.-Pad5)") (class "Default")
      (node (ref "U14") (pin "5") (pinfunction "N.C._5") (pintype "unspecified+no_connect"))
    )
    (net (code "72") (name "unconnected-(U14-N.C.-Pad6)") (class "Default")
      (node (ref "U14") (pin "6") (pinfunction "N.C._6") (pintype "unspecified+no_connect"))
    )
    (net (code "73") (name "unconnected-(U14-N.C.-Pad12)") (class "Default")
      (node (ref "U14") (pin "12") (pinfunction "N.C._12") (pintype "unspecified+no_connect"))
    )
    (net (code "74") (name "unconnected-(U14-N.C.-Pad13)") (class "Default")
      (node (ref "U14") (pin "13") (pinfunction "N.C._13") (pintype "unspecified+no_connect"))
    )
    (net (code "75") (name "unconnected-(U15-AUX_CL-Pad7)") (class "Default")
      (node (ref "U15") (pin "7") (pinfunction "AUX_CL_7") (pintype "unspecified+no_connect"))
    )
    (net (code "76") (name "unconnected-(U15-AUX_DA-Pad6)") (class "Default")
      (node (ref "U15") (pin "6") (pinfunction "AUX_DA_6") (pintype "unspecified+no_connect"))
    )
    (net (code "77") (name "unconnected-(U15-FSYNC-Pad11)") (class "Default")
      (node (ref "U15") (pin "11") (pinfunction "FSYNC_11") (pintype "unspecified+no_connect"))
    )
    (net (code "78") (name "unconnected-(U15-NC-Pad2)") (class "Default")
      (node (ref "U15") (pin "2") (pinfunction "NC_2") (pintype "unspecified+no_connect"))
    )
    (net (code "79") (name "unconnected-(U15-NC-Pad3)") (class "Default")
      (node (ref "U15") (pin "3") (pinfunction "NC_3") (pintype "unspecified+no_connect"))
    )
    (net (code "80") (name "unconnected-(U15-NC-Pad4)") (class "Default")
      (node (ref "U15") (pin "4") (pinfunction "NC_4") (pintype "unspecified+no_connect"))
    )
    (net (code "81") (name "unconnected-(U15-NC-Pad5)") (class "Default")
      (node (ref "U15") (pin "5") (pinfunction "NC_5") (pintype "unspecified+no_connect"))
    )
    (net (code "82") (name "unconnected-(U15-NC-Pad14)") (class "Default")
      (node (ref "U15") (pin "14") (pinfunction "NC_14") (pintype "unspecified+no_connect"))
    )
    (net (code "83") (name "unconnected-(U15-NC-Pad15)") (class "Default")
      (node (ref "U15") (pin "15") (pinfunction "NC_15") (pintype "unspecified+no_connect"))
    )
    (net (code "84") (name "unconnected-(U15-NC-Pad16)") (class "Default")
      (node (ref "U15") (pin "16") (pinfunction "NC_16") (pintype "unspecified+no_connect"))
    )
    (net (code "85") (name "unconnected-(U15-NC-Pad17)") (class "Default")
      (node (ref "U15") (pin "17") (pinfunction "NC_17") (pintype "unspecified+no_connect"))
    )
    (net (code "86") (name "unconnected-(U15-RESV-Pad19)") (class "Default")
      (node (ref "U15") (pin "19") (pinfunction "RESV_19") (pintype "unspecified+no_connect"))
    )
    (net (code "87") (name "unconnected-(U15-RESV-Pad21)") (class "Default")
      (node (ref "U15") (pin "21") (pinfunction "RESV_21") (pintype "unspecified+no_connect"))
    )
    (net (code "88") (name "unconnected-(U15-RESV-Pad22)") (class "Default")
      (node (ref "U15") (pin "22") (pinfunction "RESV_22") (pintype "unspecified+no_connect"))
    )
    (net (code "89") (name "unconnected-(USB1-SUB1-PadA8)") (class "Default")
      (node (ref "USB1") (pin "A8") (pinfunction "SUB1_A8") (pintype "unspecified+no_connect"))
    )
    (net (code "90") (name "unconnected-(USB1-SUB2-PadB8)") (class "Default")
      (node (ref "USB1") (pin "B8") (pinfunction "SUB2_B8") (pintype "unspecified+no_connect"))
    )
  )
)
